# sensors.net
KiCad netlist of a schematic drawn in Altium Designer
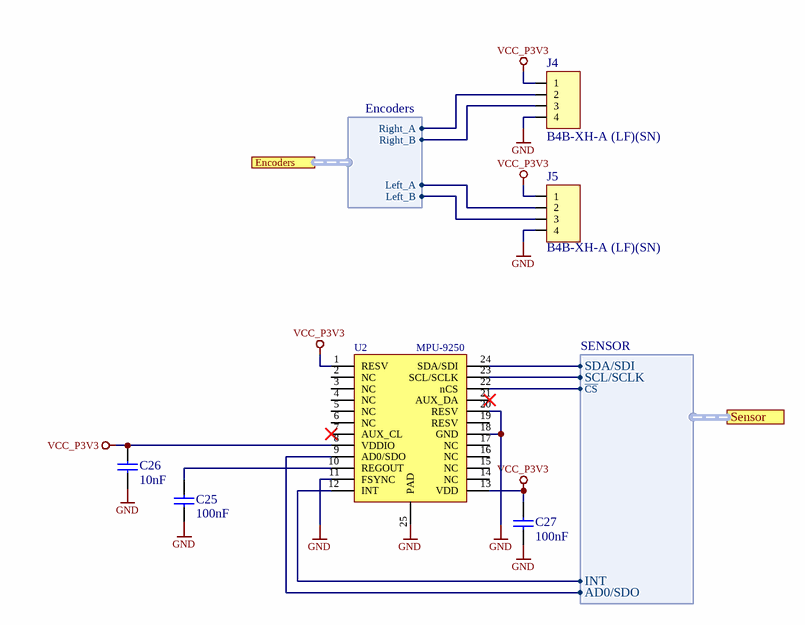
[diagram p0: sensors.SchDoc]

(export (version "E")
  (design (tool "Eeschema 10.0.6"))
  (components
    (comp (ref "C25")
      (value "100nF")
      (footprint "CAPC1005X04L")
      (description "Capacitor, X7R, ±10%")
      (fields (field (name "PART NUMBER") "C0402-100n") (field (name "PUBLISHER") "Nordic Semiconductor"))
      (libsource (lib "Nordic Passive DB") (part "CAP"))
    )
    (comp (ref "C26")
      (value "10nF")
      (footprint "CAPC1005X04L")
      (description "Capacitor, X7R, ±10%")
      (fields (field (name "PART NUMBER") "C0402-10n") (field (name "PUBLISHER") "Nordic Semiconductor"))
      (libsource (lib "Nordic Passive DB") (part "CAP"))
    )
    (comp (ref "C27")
      (value "100nF")
      (footprint "CAPC1005X04L")
      (description "Capacitor, X7R, ±10%")
      (fields (field (name "PART NUMBER") "C0402-100n") (field (name "PUBLISHER") "Nordic Semiconductor"))
      (libsource (lib "Nordic Passive DB") (part "CAP"))
    )
    (comp (ref "J4")
      (value "B4B-XH-A (LF)(SN)")
      (footprint "JST_4P")
      (libsource (lib "OVLib_64") (part "4PConnector"))
    )
    (comp (ref "J5")
      (value "B4B-XH-A (LF)(SN)")
      (footprint "JST_4P")
      (libsource (lib "OVLib_64") (part "4PConnector"))
    )
    (comp (ref "U2")
      (value "MPU-9250")
      (footprint "QFN05P40X40X02-24")
      (description "=beskrivelse")
      (libsource (lib "OVLib_64") (part "MPU-9250"))
    )
  )
  (nets
    (net (code "3") (name "/AD0{slash}SDO") (class "Default")
      (node (ref "U2") (pin "9") (pinfunction "AD0/SDO_9") (pintype "passive"))
    )
    (net (code "4") (name "/INT") (class "Default")
      (node (ref "U2") (pin "12") (pinfunction "INT_12") (pintype "passive"))
    )
    (net (code "5") (name "/Left_A") (class "Default")
      (node (ref "J5") (pin "2") (pinfunction "2_2") (pintype "passive"))
    )
    (net (code "6") (name "/Left_B") (class "Default")
      (node (ref "J5") (pin "3") (pinfunction "3_3") (pintype "passive"))
    )
    (net (code "7") (name "/Right_A") (class "Default")
      (node (ref "J4") (pin "2") (pinfunction "2_2") (pintype "passive"))
    )
    (net (code "8") (name "/Right_B") (class "Default")
      (node (ref "J4") (pin "3") (pinfunction "3_3") (pintype "passive"))
    )
    (net (code "9") (name "/SCL{slash}SCLK") (class "Default")
      (node (ref "U2") (pin "23") (pinfunction "SCL/SCLK_23") (pintype "passive"))
    )
    (net (code "10") (name "/SDA{slash}SDI") (class "Default")
      (node (ref "U2") (pin "24") (pinfunction "SDA/SDI_24") (pintype "passive"))
    )
    (net (code "13") (name "/~{CS}") (class "Default")
      (node (ref "U2") (pin "22") (pinfunction "nCS_22") (pintype "passive"))
    )
    (net (code "14") (name "GND") (class "Default")
      (node (ref "C25") (pin "2") (pinfunction "2_2") (pintype "passive"))
      (node (ref "C26") (pin "1") (pinfunction "1_1") (pintype "passive"))
      (node (ref "C27") (pin "2") (pinfunction "2_2") (pintype "passive"))
      (node (ref "J4") (pin "4") (pinfunction "4_4") (pintype "passive"))
      (node (ref "J5") (pin "4") (pinfunction "4_4") (pintype "passive"))
      (node (ref "U2") (pin "11") (pinfunction "FSYNC_11") (pintype "passive"))
      (node (ref "U2") (pin "18") (pinfunction "GND_18") (pintype "power_in"))
      (node (ref "U2") (pin "20") (pinfunction "RESV_20") (pintype "passive"))
      (node (ref "U2") (pin "25") (pinfunction "PAD_25") (pintype "passive"))
    )
    (net (code "15") (name "Net-(U2-REGOUT)") (class "Default")
      (node (ref "C25") (pin "1") (pinfunction "1_1") (pintype "passive"))
      (node (ref "U2") (pin "10") (pinfunction "REGOUT_10") (pintype "passive"))
    )
    (net (code "16") (name "VCC_P3V3") (class "Default")
      (node (ref "C26") (pin "2") (pinfunction "2_2") (pintype "passive"))
      (node (ref "C27") (pin "1") (pinfunction "1_1") (pintype "passive"))
      (node (ref "J4") (pin "1") (pinfunction "1_1") (pintype "passive"))
      (node (ref "J5") (pin "1") (pinfunction "1_1") (pintype "passive"))
      (node (ref "U2") (pin "1") (pinfunction "RESV_1") (pintype "passive"))
      (node (ref "U2") (pin "13") (pinfunction "VDD_13") (pintype "power_in"))
      (node (ref "U2") (pin "8") (pinfunction "VDDIO_8") (pintype "power_in"))
    )
    (net (code "17") (name "unconnected-(U2-AUX_CL-Pad7)") (class "Default")
      (node (ref "U2") (pin "7") (pinfunction "AUX_CL_7") (pintype "passive+no_connect"))
    )
    (net (code "18") (name "unconnected-(U2-AUX_DA-Pad21)") (class "Default")
      (node (ref "U2") (pin "21") (pinfunction "AUX_DA_21") (pintype "passive+no_connect"))
    )
    (net (code "19") (name "unconnected-(U2-NC-Pad2)") (class "Default")
      (node (ref "U2") (pin "2") (pinfunction "NC_2") (pintype "passive"))
    )
    (net (code "20") (name "unconnected-(U2-NC-Pad3)") (class "Default")
      (node (ref "U2") (pin "3") (pinfunction "NC_3") (pintype "passive"))
    )
    (net (code "21") (name "unconnected-(U2-NC-Pad4)") (class "Default")
      (node (ref "U2") (pin "4") (pinfunction "NC_4") (pintype "passive"))
    )
    (net (code "22") (name "unconnected-(U2-NC-Pad5)") (class "Default")
      (node (ref "U2") (pin "5") (pinfunction "NC_5") (pintype "passive"))
    )
    (net (code "23") (name "unconnected-(U2-NC-Pad6)") (class "Default")
      (node (ref "U2") (pin "6") (pinfunction "NC_6") (pintype "passive"))
    )
    (net (code "24") (name "unconnected-(U2-NC-Pad14)") (class "Default")
      (node (ref "U2") (pin "14") (pinfunction "NC_14") (pintype "passive"))
    )
    (net (code "25") (name "unconnected-(U2-NC-Pad15)") (class "Default")
      (node (ref "U2") (pin "15") (pinfunction "NC_15") (pintype "passive"))
    )
    (net (code "26") (name "unconnected-(U2-NC-Pad16)") (class "Default")
      (node (ref "U2") (pin "16") (pinfunction "NC_16") (pintype "passive"))
    )
    (net (code "27") (name "unconnected-(U2-NC-Pad17)") (class "Default")
      (node (ref "U2") (pin "17") (pinfunction "NC_17") (pintype "passive"))
    )
    (net (code "28") (name "unconnected-(U2-RESV-Pad19)") (class "Default")
      (node (ref "U2") (pin "19") (pinfunction "RESV_19") (pintype "passive"))
    )
  )
)
